# Teaching_instrument_mother_board_v4.net
KiCad netlist of a schematic drawn in EAGLE
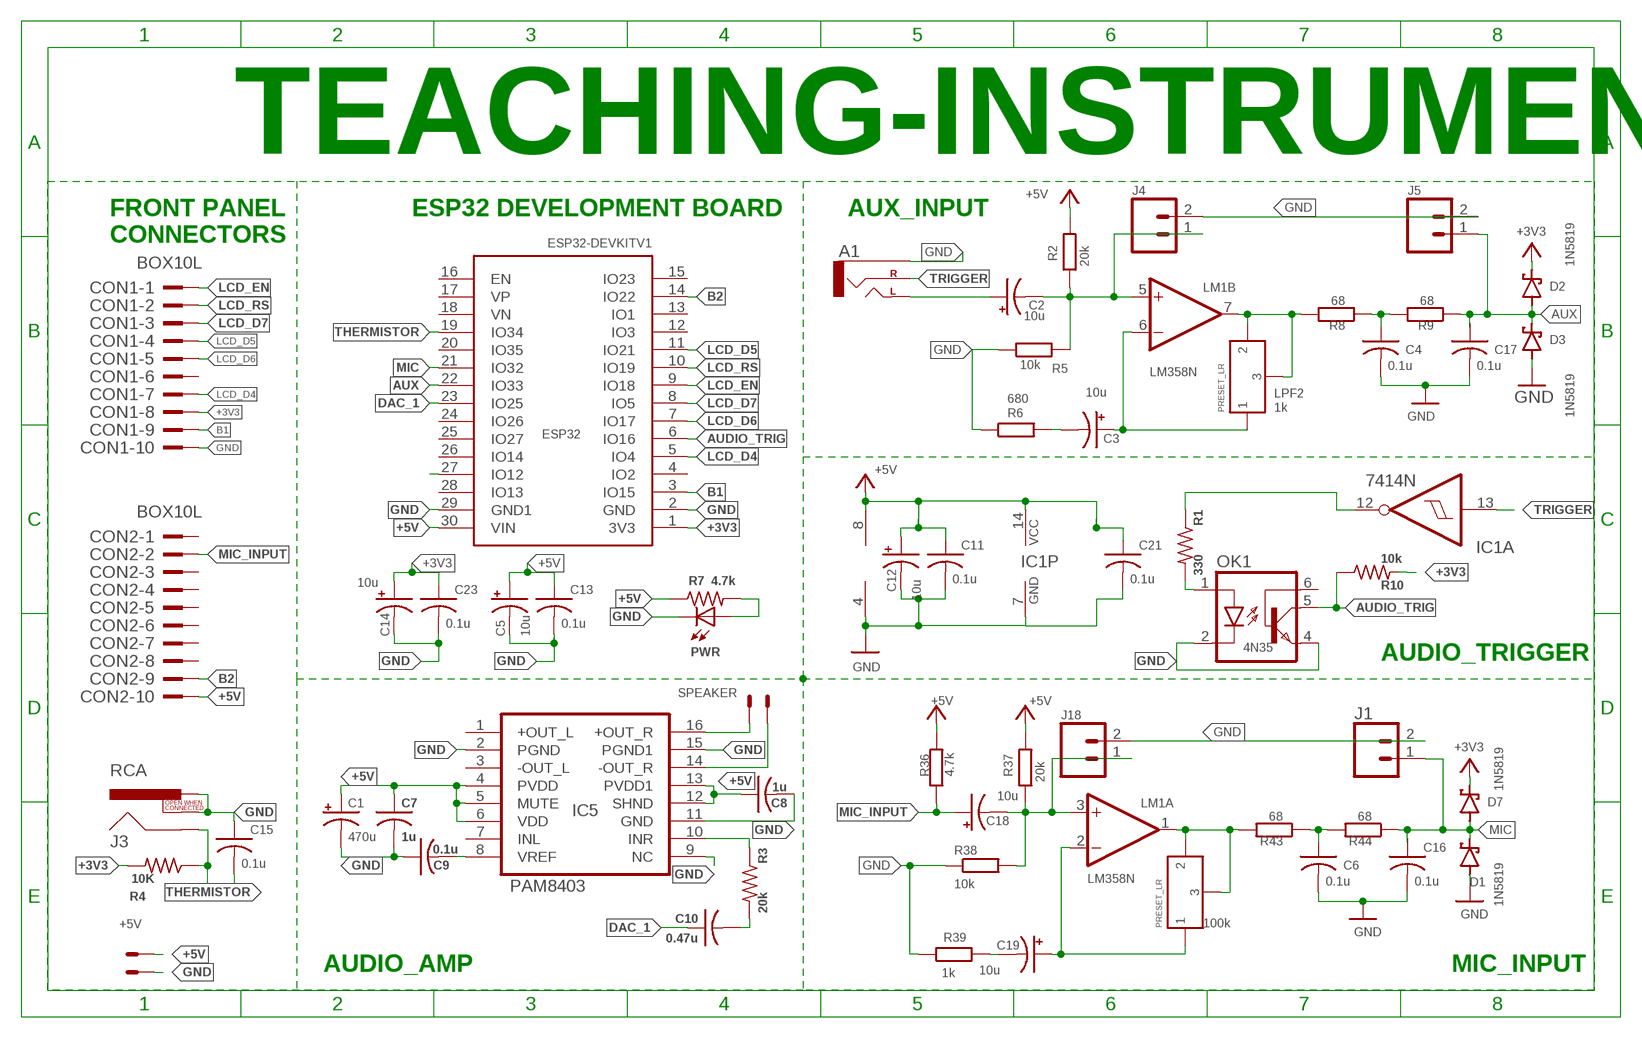
[diagram p0: schematic, sheet 1]

(export (version "E")
  (design (tool "Eeschema 10.0.6"))
  (components
    (comp (ref "100K")
      (value "PRESET_LR")
      (footprint "eagle-import:PRESET_LR")
      (libsource (lib "eagle-import") (part "PRESET_LR"))
    )
    (comp (ref "A1")
      (value "CEDT_JANUARY_2015_V5_AUDIO-JACKPTH")
      (footprint "eagle-import:CEDT_JANUARY_2015_V5_AUDIO-JACK")
      (libsource (lib "eagle-import") (part "CEDT_JANUARY_2015_V5_AUDIO-JACKPTH"))
    )
    (comp (ref "C1")
      (value "470u")
      (footprint "eagle-import:E5-10,5")
      (libsource (lib "eagle-import") (part "CPOL-USE5-10.5"))
    )
    (comp (ref "C2")
      (value "10u")
      (footprint "eagle-import:E2,5-5")
      (libsource (lib "eagle-import") (part "CPOL-USE2.5-5"))
    )
    (comp (ref "C3")
      (value "10u")
      (footprint "eagle-import:E2,5-5")
      (libsource (lib "eagle-import") (part "CPOL-USE2.5-5"))
    )
    (comp (ref "C4")
      (value "0.1u")
      (footprint "eagle-import:C025-024X044")
      (libsource (lib "eagle-import") (part "C-US025-024X044"))
    )
    (comp (ref "C5")
      (value "10u")
      (footprint "eagle-import:E2,5-5")
      (libsource (lib "eagle-import") (part "CPOL-USE2.5-5"))
    )
    (comp (ref "C6")
      (value "0.1u")
      (footprint "eagle-import:C025-024X044")
      (libsource (lib "eagle-import") (part "C-US025-024X044"))
    )
    (comp (ref "C7")
      (value "1u")
      (footprint "eagle-import:C0805")
      (libsource (lib "eagle-import") (part "CAP0805"))
    )
    (comp (ref "C8")
      (value "1u")
      (footprint "eagle-import:C0805")
      (libsource (lib "eagle-import") (part "CAP0805"))
    )
    (comp (ref "C9")
      (value "0.1u")
      (footprint "eagle-import:C0805")
      (libsource (lib "eagle-import") (part "CAP0805"))
    )
    (comp (ref "C10")
      (value "0.47u")
      (footprint "eagle-import:C0603")
      (libsource (lib "eagle-import") (part "CAP0603"))
    )
    (comp (ref "C11")
      (value "0.1u")
      (footprint "eagle-import:C025-024X044")
      (libsource (lib "eagle-import") (part "C-US025-024X044"))
    )
    (comp (ref "C12")
      (value "10u")
      (footprint "eagle-import:E2,5-5")
      (libsource (lib "eagle-import") (part "CPOL-USE2.5-5"))
    )
    (comp (ref "C13")
      (value "0.1u")
      (footprint "eagle-import:C025-024X044")
      (libsource (lib "eagle-import") (part "C-US025-024X044"))
    )
    (comp (ref "C14")
      (value "10u")
      (footprint "eagle-import:E2,5-5")
      (libsource (lib "eagle-import") (part "CPOL-USE2.5-5"))
    )
    (comp (ref "C15")
      (value "0.1u")
      (footprint "eagle-import:C025-024X044")
      (libsource (lib "eagle-import") (part "C-US025-024X044"))
    )
    (comp (ref "C16")
      (value "0.1u")
      (footprint "eagle-import:C025-024X044")
      (libsource (lib "eagle-import") (part "C-US025-024X044"))
    )
    (comp (ref "C17")
      (value "0.1u")
      (footprint "eagle-import:C025-024X044")
      (libsource (lib "eagle-import") (part "C-US025-024X044"))
    )
    (comp (ref "C18")
      (value "10u")
      (footprint "eagle-import:E2,5-5")
      (libsource (lib "eagle-import") (part "CPOL-USE2.5-5"))
    )
    (comp (ref "C19")
      (value "10u")
      (footprint "eagle-import:E2,5-5")
      (libsource (lib "eagle-import") (part "CPOL-USE2.5-5"))
    )
    (comp (ref "C21")
      (value "0.1u")
      (footprint "eagle-import:C025-024X044")
      (libsource (lib "eagle-import") (part "C-US025-024X044"))
    )
    (comp (ref "C23")
      (value "0.1u")
      (footprint "eagle-import:C025-024X044")
      (libsource (lib "eagle-import") (part "C-US025-024X044"))
    )
    (comp (ref "CON1")
      (value "BOX10L")
      (footprint "eagle-import:BOX10L")
      (libsource (lib "eagle-import") (part "BOX10L"))
    )
    (comp (ref "CON2")
      (value "BOX10L")
      (footprint "eagle-import:BOX10L")
      (libsource (lib "eagle-import") (part "BOX10L"))
    )
    (comp (ref "D1")
      (value "1N5819")
      (footprint "eagle-import:DO41-7.6")
      (libsource (lib "eagle-import") (part "1N5819-B"))
    )
    (comp (ref "D2")
      (value "1N5819")
      (footprint "eagle-import:DO41-7.6")
      (libsource (lib "eagle-import") (part "1N5819-B"))
    )
    (comp (ref "D3")
      (value "1N5819")
      (footprint "eagle-import:DO41-7.6")
      (libsource (lib "eagle-import") (part "1N5819-B"))
    )
    (comp (ref "D7")
      (value "1N5819")
      (footprint "eagle-import:DO41-7.6")
      (libsource (lib "eagle-import") (part "1N5819-B"))
    )
    (comp (ref "ESP32")
      (value "ESP32-DEVKITV1_ESP32DEVKITV1ESP32")
      (footprint "eagle-import:ESP32")
      (libsource (lib "eagle-import") (part "ESP32-DEVKITV1_ESP32DEVKITV1ESP32"))
    )
    (comp (ref "IC1")
      (value "7414N")
      (footprint "eagle-import:DIL14")
      (libsource (lib "eagle-import") (part "7414N"))
    )
    (comp (ref "IC5")
      (value "PAM8403")
      (footprint "eagle-import:SOP-16")
      (libsource (lib "eagle-import") (part "PAM8403"))
    )
    (comp (ref "J1")
      (value "CONN_02")
      (footprint "eagle-import:1X02")
      (libsource (lib "eagle-import") (part "CONN_02"))
    )
    (comp (ref "J3")
      (value "RCA")
      (footprint "eagle-import:RCA")
      (libsource (lib "eagle-import") (part "RCA"))
    )
    (comp (ref "J4")
      (value "CONN_02")
      (footprint "eagle-import:1X02")
      (libsource (lib "eagle-import") (part "CONN_02"))
    )
    (comp (ref "J5")
      (value "CONN_02")
      (footprint "eagle-import:1X02")
      (libsource (lib "eagle-import") (part "CONN_02"))
    )
    (comp (ref "J18")
      (value "CONN_02")
      (footprint "eagle-import:1X02")
      (libsource (lib "eagle-import") (part "CONN_02"))
    )
    (comp (ref "LM1")
      (value "LM358N")
      (footprint "eagle-import:DIL08")
      (libsource (lib "eagle-import") (part "LM358N"))
    )
    (comp (ref "OK1")
      (value "4N35")
      (footprint "eagle-import:DIL06")
      (fields (field (name "MF") "FAIRCHILD SEMICONDUCTOR"))
      (libsource (lib "eagle-import") (part "4N35"))
    )
    (comp (ref "PWR")
      (value "LED3MM")
      (footprint "eagle-import:LED3MM")
      (libsource (lib "eagle-import") (part "LED3MM"))
    )
    (comp (ref "R1")
      (value "330")
      (footprint "eagle-import:M0805")
      (libsource (lib "eagle-import") (part "rcl_334_R-US_M0805"))
    )
    (comp (ref "R2")
      (value "20k")
      (footprint "eagle-import:0207_10")
      (libsource (lib "eagle-import") (part "R-EU_0207/10"))
    )
    (comp (ref "R3")
      (value "20k")
      (footprint "eagle-import:0207_10")
      (libsource (lib "eagle-import") (part "rcl_334_R-US_0207/10"))
    )
    (comp (ref "R4")
      (value "10K")
      (footprint "eagle-import:0207_10")
      (libsource (lib "eagle-import") (part "rcl_334_R-US_0207/10"))
    )
    (comp (ref "R5")
      (value "10k")
      (footprint "eagle-import:0207_10")
      (libsource (lib "eagle-import") (part "R-EU_0207/10"))
    )
    (comp (ref "R6")
      (value "680")
      (footprint "eagle-import:0207_10")
      (libsource (lib "eagle-import") (part "R-EU_0207/10"))
    )
    (comp (ref "R7")
      (value "4.7k")
      (footprint "eagle-import:0207_10")
      (libsource (lib "eagle-import") (part "R-US_0207/10"))
    )
    (comp (ref "R8")
      (value "68")
      (footprint "eagle-import:0207_10")
      (libsource (lib "eagle-import") (part "R-EU_0207/10"))
    )
    (comp (ref "R9")
      (value "68")
      (footprint "eagle-import:0207_10")
      (libsource (lib "eagle-import") (part "R-EU_0207/10"))
    )
    (comp (ref "R10")
      (value "10k")
      (footprint "eagle-import:M0805")
      (libsource (lib "eagle-import") (part "rcl_334_R-US_M0805"))
    )
    (comp (ref "R36")
      (value "4.7k")
      (footprint "eagle-import:0207_10")
      (libsource (lib "eagle-import") (part "R-EU_0207/10"))
    )
    (comp (ref "R37")
      (value "20k")
      (footprint "eagle-import:0207_10")
      (libsource (lib "eagle-import") (part "R-EU_0207/10"))
    )
    (comp (ref "R38")
      (value "10k")
      (footprint "eagle-import:0207_10")
      (libsource (lib "eagle-import") (part "R-EU_0207/10"))
    )
    (comp (ref "R39")
      (value "1k")
      (footprint "eagle-import:0207_10")
      (libsource (lib "eagle-import") (part "R-EU_0207/10"))
    )
    (comp (ref "R43")
      (value "68")
      (footprint "eagle-import:0207_10")
      (libsource (lib "eagle-import") (part "R-EU_0207/10"))
    )
    (comp (ref "R44")
      (value "68")
      (footprint "eagle-import:0207_10")
      (libsource (lib "eagle-import") (part "R-EU_0207/10"))
    )
    (comp (ref "SPEAKER")
      (value "SPEAKER")
      (footprint "eagle-import:JST-XH-02-PACKAGE-LONG-PAD")
      (libsource (lib "eagle-import") (part "JST-XH-02-PIN-LONG-PAD"))
    )
    (comp (ref "U$3")
      (value "PRESET_LR")
      (footprint "eagle-import:PRESET_LR")
      (libsource (lib "eagle-import") (part "PRESET_LR"))
    )
    (comp (ref "X1")
      (value "+5V")
      (footprint "eagle-import:JST-XH-02-PACKAGE-LONG-PAD")
      (libsource (lib "eagle-import") (part "JST-XH-02-PIN-LONG-PAD"))
    )
  )
  (nets
    (net (code "1") (name "+3V3") (class "Default")
      (node (ref "C14") (pin "+") (pinfunction "+_+") (pintype "passive"))
      (node (ref "C23") (pin "1") (pinfunction "1_1") (pintype "passive"))
      (node (ref "CON1") (pin "8") (pinfunction "KL_8") (pintype "passive"))
      (node (ref "D2") (pin "C") (pinfunction "C_C") (pintype "passive"))
      (node (ref "D7") (pin "C") (pinfunction "C_C") (pintype "passive"))
      (node (ref "ESP32") (pin "1") (pinfunction "3V3_1") (pintype "bidirectional"))
      (node (ref "R10") (pin "2") (pinfunction "2_2") (pintype "passive"))
      (node (ref "R4") (pin "2") (pinfunction "2_2") (pintype "passive"))
    )
    (net (code "2") (name "+5V") (class "Default")
      (node (ref "C1") (pin "+") (pinfunction "+_+") (pintype "passive"))
      (node (ref "C11") (pin "1") (pinfunction "1_1") (pintype "passive"))
      (node (ref "C12") (pin "+") (pinfunction "+_+") (pintype "passive"))
      (node (ref "C13") (pin "1") (pinfunction "1_1") (pintype "passive"))
      (node (ref "C21") (pin "1") (pinfunction "1_1") (pintype "passive"))
      (node (ref "C5") (pin "+") (pinfunction "+_+") (pintype "passive"))
      (node (ref "C7") (pin "1") (pinfunction "1_1") (pintype "passive"))
      (node (ref "C8") (pin "1") (pinfunction "1_1") (pintype "passive"))
      (node (ref "CON2") (pin "10") (pinfunction "KL_10") (pintype "passive"))
      (node (ref "ESP32") (pin "30") (pinfunction "VIN_30") (pintype "bidirectional"))
      (node (ref "IC1") (pin "14") (pinfunction "VCC_14") (pintype "power_in"))
      (node (ref "IC5") (pin "12") (pinfunction "SHND_12") (pintype "output"))
      (node (ref "IC5") (pin "13") (pinfunction "PVDD1_13") (pintype "output"))
      (node (ref "IC5") (pin "4") (pinfunction "PVDD_4") (pintype "input"))
      (node (ref "IC5") (pin "5") (pinfunction "MUTE_5") (pintype "input"))
      (node (ref "IC5") (pin "6") (pinfunction "VDD_6") (pintype "input"))
      (node (ref "LM1") (pin "8") (pinfunction "V+_8") (pintype "power_in"))
      (node (ref "R2") (pin "2") (pinfunction "2_2") (pintype "passive"))
      (node (ref "R36") (pin "2") (pinfunction "2_2") (pintype "passive"))
      (node (ref "R37") (pin "2") (pinfunction "2_2") (pintype "passive"))
      (node (ref "R7") (pin "1") (pinfunction "1_1") (pintype "passive"))
      (node (ref "X1") (pin "2") (pinfunction "S_2") (pintype "passive"))
    )
    (net (code "3") (name "/LPF2") (class "Default")
      (node (ref "LM1") (pin "7") (pinfunction "OUT_7") (pintype "output"))
      (node (ref "R8") (pin "2") (pinfunction "2_2") (pintype "passive"))
      (node (ref "U$3") (pin "P$2") (pinfunction "2_P$2") (pintype "passive"))
      (node (ref "U$3") (pin "P$3") (pinfunction "3_P$3") (pintype "passive"))
    )
    (net (code "4") (name "AUDIO_TRIG") (class "Default")
      (node (ref "ESP32") (pin "6") (pinfunction "IO16_6") (pintype "bidirectional"))
      (node (ref "OK1") (pin "5") (pinfunction "COL_5") (pintype "passive"))
      (node (ref "R10") (pin "1") (pinfunction "1_1") (pintype "passive"))
    )
    (net (code "5") (name "AUX") (class "Default")
      (node (ref "C17") (pin "1") (pinfunction "1_1") (pintype "passive"))
      (node (ref "D2") (pin "A") (pinfunction "A_A") (pintype "passive"))
      (node (ref "D3") (pin "C") (pinfunction "C_C") (pintype "passive"))
      (node (ref "ESP32") (pin "22") (pinfunction "IO33_22") (pintype "bidirectional"))
      (node (ref "J5") (pin "1") (pinfunction "1_1") (pintype "passive"))
      (node (ref "R9") (pin "1") (pinfunction "1_1") (pintype "passive"))
    )
    (net (code "6") (name "B1") (class "Default")
      (node (ref "CON1") (pin "9") (pinfunction "KL_9") (pintype "passive"))
      (node (ref "ESP32") (pin "3") (pinfunction "IO15_3") (pintype "bidirectional"))
    )
    (net (code "7") (name "B2") (class "Default")
      (node (ref "CON2") (pin "9") (pinfunction "KL_9") (pintype "passive"))
      (node (ref "ESP32") (pin "14") (pinfunction "IO22_14") (pintype "bidirectional"))
    )
    (net (code "8") (name "DAC_1") (class "Default")
      (node (ref "C10") (pin "1") (pinfunction "1_1") (pintype "passive"))
      (node (ref "ESP32") (pin "23") (pinfunction "IO25_23") (pintype "bidirectional"))
    )
    (net (code "9") (name "GND") (class "Default")
      (node (ref "A1") (pin "SLEEVE") (pinfunction "SLEEVE_SLEEVE") (pintype "bidirectional"))
      (node (ref "C1") (pin "-") (pinfunction "-_-") (pintype "passive"))
      (node (ref "C11") (pin "2") (pinfunction "2_2") (pintype "passive"))
      (node (ref "C12") (pin "-") (pinfunction "-_-") (pintype "passive"))
      (node (ref "C13") (pin "2") (pinfunction "2_2") (pintype "passive"))
      (node (ref "C14") (pin "-") (pinfunction "-_-") (pintype "passive"))
      (node (ref "C15") (pin "1") (pinfunction "1_1") (pintype "passive"))
      (node (ref "C16") (pin "2") (pinfunction "2_2") (pintype "passive"))
      (node (ref "C17") (pin "2") (pinfunction "2_2") (pintype "passive"))
      (node (ref "C21") (pin "2") (pinfunction "2_2") (pintype "passive"))
      (node (ref "C23") (pin "2") (pinfunction "2_2") (pintype "passive"))
      (node (ref "C4") (pin "2") (pinfunction "2_2") (pintype "passive"))
      (node (ref "C5") (pin "-") (pinfunction "-_-") (pintype "passive"))
      (node (ref "C6") (pin "2") (pinfunction "2_2") (pintype "passive"))
      (node (ref "C7") (pin "2") (pinfunction "2_2") (pintype "passive"))
      (node (ref "C8") (pin "2") (pinfunction "2_2") (pintype "passive"))
      (node (ref "C9") (pin "1") (pinfunction "1_1") (pintype "passive"))
      (node (ref "CON1") (pin "10") (pinfunction "KL_10") (pintype "passive"))
      (node (ref "D1") (pin "A") (pinfunction "A_A") (pintype "passive"))
      (node (ref "D3") (pin "A") (pinfunction "A_A") (pintype "passive"))
      (node (ref "ESP32") (pin "2") (pinfunction "GND_2") (pintype "bidirectional"))
      (node (ref "ESP32") (pin "29") (pinfunction "GND1_29") (pintype "bidirectional"))
      (node (ref "IC1") (pin "7") (pinfunction "GND_7") (pintype "power_in"))
      (node (ref "IC5") (pin "11") (pinfunction "GND_11") (pintype "output"))
      (node (ref "IC5") (pin "15") (pinfunction "PGND1_15") (pintype "output"))
      (node (ref "IC5") (pin "2") (pinfunction "PGND_2") (pintype "input"))
      (node (ref "IC5") (pin "9") (pinfunction "NC_9") (pintype "output"))
      (node (ref "J1") (pin "2") (pinfunction "2_2") (pintype "passive"))
      (node (ref "J18") (pin "2") (pinfunction "2_2") (pintype "passive"))
      (node (ref "J3") (pin "PIN") (pinfunction "PIN_PIN") (pintype "bidirectional"))
      (node (ref "J3") (pin "SWITCH") (pinfunction "SWITCH_SWITCH") (pintype "bidirectional"))
      (node (ref "J4") (pin "2") (pinfunction "2_2") (pintype "passive"))
      (node (ref "J5") (pin "2") (pinfunction "2_2") (pintype "passive"))
      (node (ref "LM1") (pin "4") (pinfunction "V-_4") (pintype "power_in"))
      (node (ref "OK1") (pin "2") (pinfunction "C_2") (pintype "passive"))
      (node (ref "OK1") (pin "4") (pinfunction "EMI_4") (pintype "passive"))
      (node (ref "PWR") (pin "K") (pinfunction "C_K") (pintype "passive"))
      (node (ref "R38") (pin "1") (pinfunction "1_1") (pintype "passive"))
      (node (ref "R39") (pin "1") (pinfunction "1_1") (pintype "passive"))
      (node (ref "R5") (pin "1") (pinfunction "1_1") (pintype "passive"))
      (node (ref "R6") (pin "1") (pinfunction "1_1") (pintype "passive"))
      (node (ref "X1") (pin "1") (pinfunction "S_1") (pintype "passive"))
    )
    (net (code "10") (name "LCD_D4") (class "Default")
      (node (ref "CON1") (pin "7") (pinfunction "KL_7") (pintype "passive"))
      (node (ref "ESP32") (pin "5") (pinfunction "IO4_5") (pintype "bidirectional"))
    )
    (net (code "11") (name "LCD_D5") (class "Default")
      (node (ref "CON1") (pin "4") (pinfunction "KL_4") (pintype "passive"))
      (node (ref "ESP32") (pin "11") (pinfunction "IO21_11") (pintype "bidirectional"))
    )
    (net (code "12") (name "LCD_D6") (class "Default")
      (node (ref "CON1") (pin "5") (pinfunction "KL_5") (pintype "passive"))
      (node (ref "ESP32") (pin "7") (pinfunction "IO17_7") (pintype "bidirectional"))
    )
    (net (code "13") (name "LCD_D7") (class "Default")
      (node (ref "CON1") (pin "3") (pinfunction "KL_3") (pintype "passive"))
      (node (ref "ESP32") (pin "8") (pinfunction "IO5_8") (pintype "bidirectional"))
    )
    (net (code "14") (name "LCD_EN") (class "Default")
      (node (ref "CON1") (pin "1") (pinfunction "KL_1") (pintype "passive"))
      (node (ref "ESP32") (pin "9") (pinfunction "IO18_9") (pintype "bidirectional"))
    )
    (net (code "15") (name "LCD_RS") (class "Default")
      (node (ref "CON1") (pin "2") (pinfunction "KL_2") (pintype "passive"))
      (node (ref "ESP32") (pin "10") (pinfunction "IO19_10") (pintype "bidirectional"))
    )
    (net (code "16") (name "MIC") (class "Default")
      (node (ref "C16") (pin "1") (pinfunction "1_1") (pintype "passive"))
      (node (ref "D1") (pin "C") (pinfunction "C_C") (pintype "passive"))
      (node (ref "D7") (pin "A") (pinfunction "A_A") (pintype "passive"))
      (node (ref "ESP32") (pin "21") (pinfunction "IO32_21") (pintype "bidirectional"))
      (node (ref "J1") (pin "1") (pinfunction "1_1") (pintype "passive"))
      (node (ref "R44") (pin "1") (pinfunction "1_1") (pintype "passive"))
    )
    (net (code "17") (name "MIC_INPUT") (class "Default")
      (node (ref "C18") (pin "+") (pinfunction "+_+") (pintype "passive"))
      (node (ref "CON2") (pin "2") (pinfunction "KL_2") (pintype "passive"))
      (node (ref "R36") (pin "1") (pinfunction "1_1") (pintype "passive"))
    )
    (net (code "18") (name "Net-(100K-1)") (class "Default")
      (node (ref "100K") (pin "P$1") (pinfunction "1_P$1") (pintype "passive"))
      (node (ref "C19") (pin "+") (pinfunction "+_+") (pintype "passive"))
      (node (ref "LM1") (pin "2") (pinfunction "-IN_2") (pintype "input"))
    )
    (net (code "19") (name "Net-(100K-2)") (class "Default")
      (node (ref "100K") (pin "P$2") (pinfunction "2_P$2") (pintype "passive"))
      (node (ref "100K") (pin "P$3") (pinfunction "3_P$3") (pintype "passive"))
      (node (ref "LM1") (pin "1") (pinfunction "OUT_1") (pintype "output"))
      (node (ref "R43") (pin "2") (pinfunction "2_2") (pintype "passive"))
    )
    (net (code "20") (name "Net-(A1-LEFT)") (class "Default")
      (node (ref "A1") (pin "TIP") (pinfunction "LEFT_TIP") (pintype "bidirectional"))
      (node (ref "C2") (pin "+") (pinfunction "+_+") (pintype "passive"))
    )
    (net (code "21") (name "Net-(C3-Pad-)") (class "Default")
      (node (ref "C3") (pin "-") (pinfunction "-_-") (pintype "passive"))
      (node (ref "R6") (pin "2") (pinfunction "2_2") (pintype "passive"))
    )
    (net (code "22") (name "Net-(C4-Pad1)") (class "Default")
      (node (ref "C4") (pin "1") (pinfunction "1_1") (pintype "passive"))
      (node (ref "R8") (pin "1") (pinfunction "1_1") (pintype "passive"))
      (node (ref "R9") (pin "2") (pinfunction "2_2") (pintype "passive"))
    )
    (net (code "23") (name "Net-(C6-Pad1)") (class "Default")
      (node (ref "C6") (pin "1") (pinfunction "1_1") (pintype "passive"))
      (node (ref "R43") (pin "1") (pinfunction "1_1") (pintype "passive"))
      (node (ref "R44") (pin "2") (pinfunction "2_2") (pintype "passive"))
    )
    (net (code "24") (name "Net-(C10-Pad2)") (class "Default")
      (node (ref "C10") (pin "2") (pinfunction "2_2") (pintype "passive"))
      (node (ref "R3") (pin "2") (pinfunction "2_2") (pintype "passive"))
    )
    (net (code "25") (name "Net-(C19-Pad-)") (class "Default")
      (node (ref "C19") (pin "-") (pinfunction "-_-") (pintype "passive"))
      (node (ref "R39") (pin "2") (pinfunction "2_2") (pintype "passive"))
    )
    (net (code "26") (name "Net-(IC1A-O)") (class "Default")
      (node (ref "IC1") (pin "12") (pinfunction "O_12") (pintype "output"))
      (node (ref "R1") (pin "1") (pinfunction "1_1") (pintype "passive"))
    )
    (net (code "27") (name "Net-(IC5-+OUT_R)") (class "Default")
      (node (ref "IC5") (pin "16") (pinfunction "+OUT_R_16") (pintype "output"))
      (node (ref "SPEAKER") (pin "2") (pinfunction "S_2") (pintype "passive"))
    )
    (net (code "28") (name "Net-(IC5--OUT_R)") (class "Default")
      (node (ref "IC5") (pin "14") (pinfunction "-OUT_R_14") (pintype "output"))
      (node (ref "SPEAKER") (pin "1") (pinfunction "S_1") (pintype "passive"))
    )
    (net (code "29") (name "Net-(IC5-INR)") (class "Default")
      (node (ref "IC5") (pin "10") (pinfunction "INR_10") (pintype "output"))
      (node (ref "R3") (pin "1") (pinfunction "1_1") (pintype "passive"))
    )
    (net (code "30") (name "Net-(IC5-VREF)") (class "Default")
      (node (ref "C9") (pin "2") (pinfunction "2_2") (pintype "passive"))
      (node (ref "IC5") (pin "8") (pinfunction "VREF_8") (pintype "input"))
    )
    (net (code "31") (name "Net-(LM1A-+IN)") (class "Default")
      (node (ref "C18") (pin "-") (pinfunction "-_-") (pintype "passive"))
      (node (ref "J18") (pin "1") (pinfunction "1_1") (pintype "passive"))
      (node (ref "LM1") (pin "3") (pinfunction "+IN_3") (pintype "input"))
      (node (ref "R37") (pin "1") (pinfunction "1_1") (pintype "passive"))
      (node (ref "R38") (pin "2") (pinfunction "2_2") (pintype "passive"))
    )
    (net (code "32") (name "Net-(LM1B-+IN)") (class "Default")
      (node (ref "C2") (pin "-") (pinfunction "-_-") (pintype "passive"))
      (node (ref "J4") (pin "1") (pinfunction "1_1") (pintype "passive"))
      (node (ref "LM1") (pin "5") (pinfunction "+IN_5") (pintype "input"))
      (node (ref "R2") (pin "1") (pinfunction "1_1") (pintype "passive"))
      (node (ref "R5") (pin "2") (pinfunction "2_2") (pintype "passive"))
    )
    (net (code "33") (name "Net-(LM1B--IN)") (class "Default")
      (node (ref "C3") (pin "+") (pinfunction "+_+") (pintype "passive"))
      (node (ref "LM1") (pin "6") (pinfunction "-IN_6") (pintype "input"))
      (node (ref "U$3") (pin "P$1") (pinfunction "1_P$1") (pintype "passive"))
    )
    (net (code "34") (name "Net-(OK1-A)") (class "Default")
      (node (ref "OK1") (pin "1") (pinfunction "A_1") (pintype "passive"))
      (node (ref "R1") (pin "2") (pinfunction "2_2") (pintype "passive"))
    )
    (net (code "35") (name "Net-(PWR-PadA)") (class "Default")
      (node (ref "PWR") (pin "A") (pinfunction "A_A") (pintype "passive"))
      (node (ref "R7") (pin "2") (pinfunction "2_2") (pintype "passive"))
    )
    (net (code "36") (name "THERMISTOR") (class "Default")
      (node (ref "C15") (pin "2") (pinfunction "2_2") (pintype "passive"))
      (node (ref "ESP32") (pin "19") (pinfunction "IO34_19") (pintype "bidirectional"))
      (node (ref "J3") (pin "SHELL") (pinfunction "SHELL_SHELL") (pintype "bidirectional"))
      (node (ref "R4") (pin "1") (pinfunction "1_1") (pintype "passive"))
    )
    (net (code "37") (name "TRIGGER") (class "Default")
      (node (ref "A1") (pin "RING") (pinfunction "RIGHT_RING") (pintype "bidirectional"))
      (node (ref "IC1") (pin "13") (pinfunction "I_13") (pintype "input"))
    )
    (net (code "38") (name "unconnected-(CON1G-KL-Pad6)") (class "Default")
      (node (ref "CON1") (pin "6") (pinfunction "KL_6") (pintype "passive"))
    )
    (net (code "39") (name "unconnected-(CON2A-KL-Pad1)") (class "Default")
      (node (ref "CON2") (pin "1") (pinfunction "KL_1") (pintype "passive"))
    )
    (net (code "40") (name "unconnected-(CON2D-KL-Pad3)") (class "Default")
      (node (ref "CON2") (pin "3") (pinfunction "KL_3") (pintype "passive"))
    )
    (net (code "41") (name "unconnected-(CON2E-KL-Pad4)") (class "Default")
      (node (ref "CON2") (pin "4") (pinfunction "KL_4") (pintype "passive"))
    )
    (net (code "42") (name "unconnected-(CON2F-KL-Pad5)") (class "Default")
      (node (ref "CON2") (pin "5") (pinfunction "KL_5") (pintype "passive"))
    )
    (net (code "43") (name "unconnected-(CON2G-KL-Pad6)") (class "Default")
      (node (ref "CON2") (pin "6") (pinfunction "KL_6") (pintype "passive"))
    )
    (net (code "44") (name "unconnected-(CON2H-KL-Pad7)") (class "Default")
      (node (ref "CON2") (pin "7") (pinfunction "KL_7") (pintype "passive"))
    )
    (net (code "45") (name "unconnected-(CON2I-KL-Pad8)") (class "Default")
      (node (ref "CON2") (pin "8") (pinfunction "KL_8") (pintype "passive"))
    )
    (net (code "46") (name "unconnected-(ESP32-EN-Pad16)") (class "Default")
      (node (ref "ESP32") (pin "16") (pinfunction "EN_16") (pintype "bidirectional"))
    )
    (net (code "47") (name "unconnected-(ESP32-IO1-Pad13)") (class "Default")
      (node (ref "ESP32") (pin "13") (pinfunction "IO1_13") (pintype "bidirectional"))
    )
    (net (code "48") (name "unconnected-(ESP32-IO2-Pad4)") (class "Default")
      (node (ref "ESP32") (pin "4") (pinfunction "IO2_4") (pintype "bidirectional"))
    )
    (net (code "49") (name "unconnected-(ESP32-IO3-Pad12)") (class "Default")
      (node (ref "ESP32") (pin "12") (pinfunction "IO3_12") (pintype "bidirectional"))
    )
    (net (code "50") (name "unconnected-(ESP32-IO12-Pad27)") (class "Default")
      (node (ref "ESP32") (pin "27") (pinfunction "IO12_27") (pintype "bidirectional"))
    )
    (net (code "51") (name "unconnected-(ESP32-IO13-Pad28)") (class "Default")
      (node (ref "ESP32") (pin "28") (pinfunction "IO13_28") (pintype "bidirectional"))
    )
    (net (code "52") (name "unconnected-(ESP32-IO14-Pad26)") (class "Default")
      (node (ref "ESP32") (pin "26") (pinfunction "IO14_26") (pintype "bidirectional"))
    )
    (net (code "53") (name "unconnected-(ESP32-IO23-Pad15)") (class "Default")
      (node (ref "ESP32") (pin "15") (pinfunction "IO23_15") (pintype "bidirectional"))
    )
    (net (code "54") (name "unconnected-(ESP32-IO26-Pad24)") (class "Default")
      (node (ref "ESP32") (pin "24") (pinfunction "IO26_24") (pintype "bidirectional"))
    )
    (net (code "55") (name "unconnected-(ESP32-IO27-Pad25)") (class "Default")
      (node (ref "ESP32") (pin "25") (pinfunction "IO27_25") (pintype "bidirectional"))
    )
    (net (code "56") (name "unconnected-(ESP32-IO35-Pad20)") (class "Default")
      (node (ref "ESP32") (pin "20") (pinfunction "IO35_20") (pintype "bidirectional"))
    )
    (net (code "57") (name "unconnected-(ESP32-VN-Pad18)") (class "Default")
      (node (ref "ESP32") (pin "18") (pinfunction "VN_18") (pintype "bidirectional"))
    )
    (net (code "58") (name "unconnected-(ESP32-VP-Pad17)") (class "Default")
      (node (ref "ESP32") (pin "17") (pinfunction "VP_17") (pintype "bidirectional"))
    )
    (net (code "59") (name "unconnected-(IC5-+OUT_L-Pad1)") (class "Default")
      (node (ref "IC5") (pin "1") (pinfunction "+OUT_L_1") (pintype "input"))
    )
    (net (code "60") (name "unconnected-(IC5--OUT_L-Pad3)") (class "Default")
      (node (ref "IC5") (pin "3") (pinfunction "-OUT_L_3") (pintype "input"))
    )
    (net (code "61") (name "unconnected-(IC5-INL-Pad7)") (class "Default")
      (node (ref "IC5") (pin "7") (pinfunction "INL_7") (pintype "input"))
    )
    (net (code "62") (name "unconnected-(OK1-BAS-Pad6)") (class "Default")
      (node (ref "OK1") (pin "6") (pinfunction "BAS_6") (pintype "passive"))
    )
  )
)
